# trinamic-controller-dribbler.net
KiCad netlist of a schematic drawn in Altium Designer
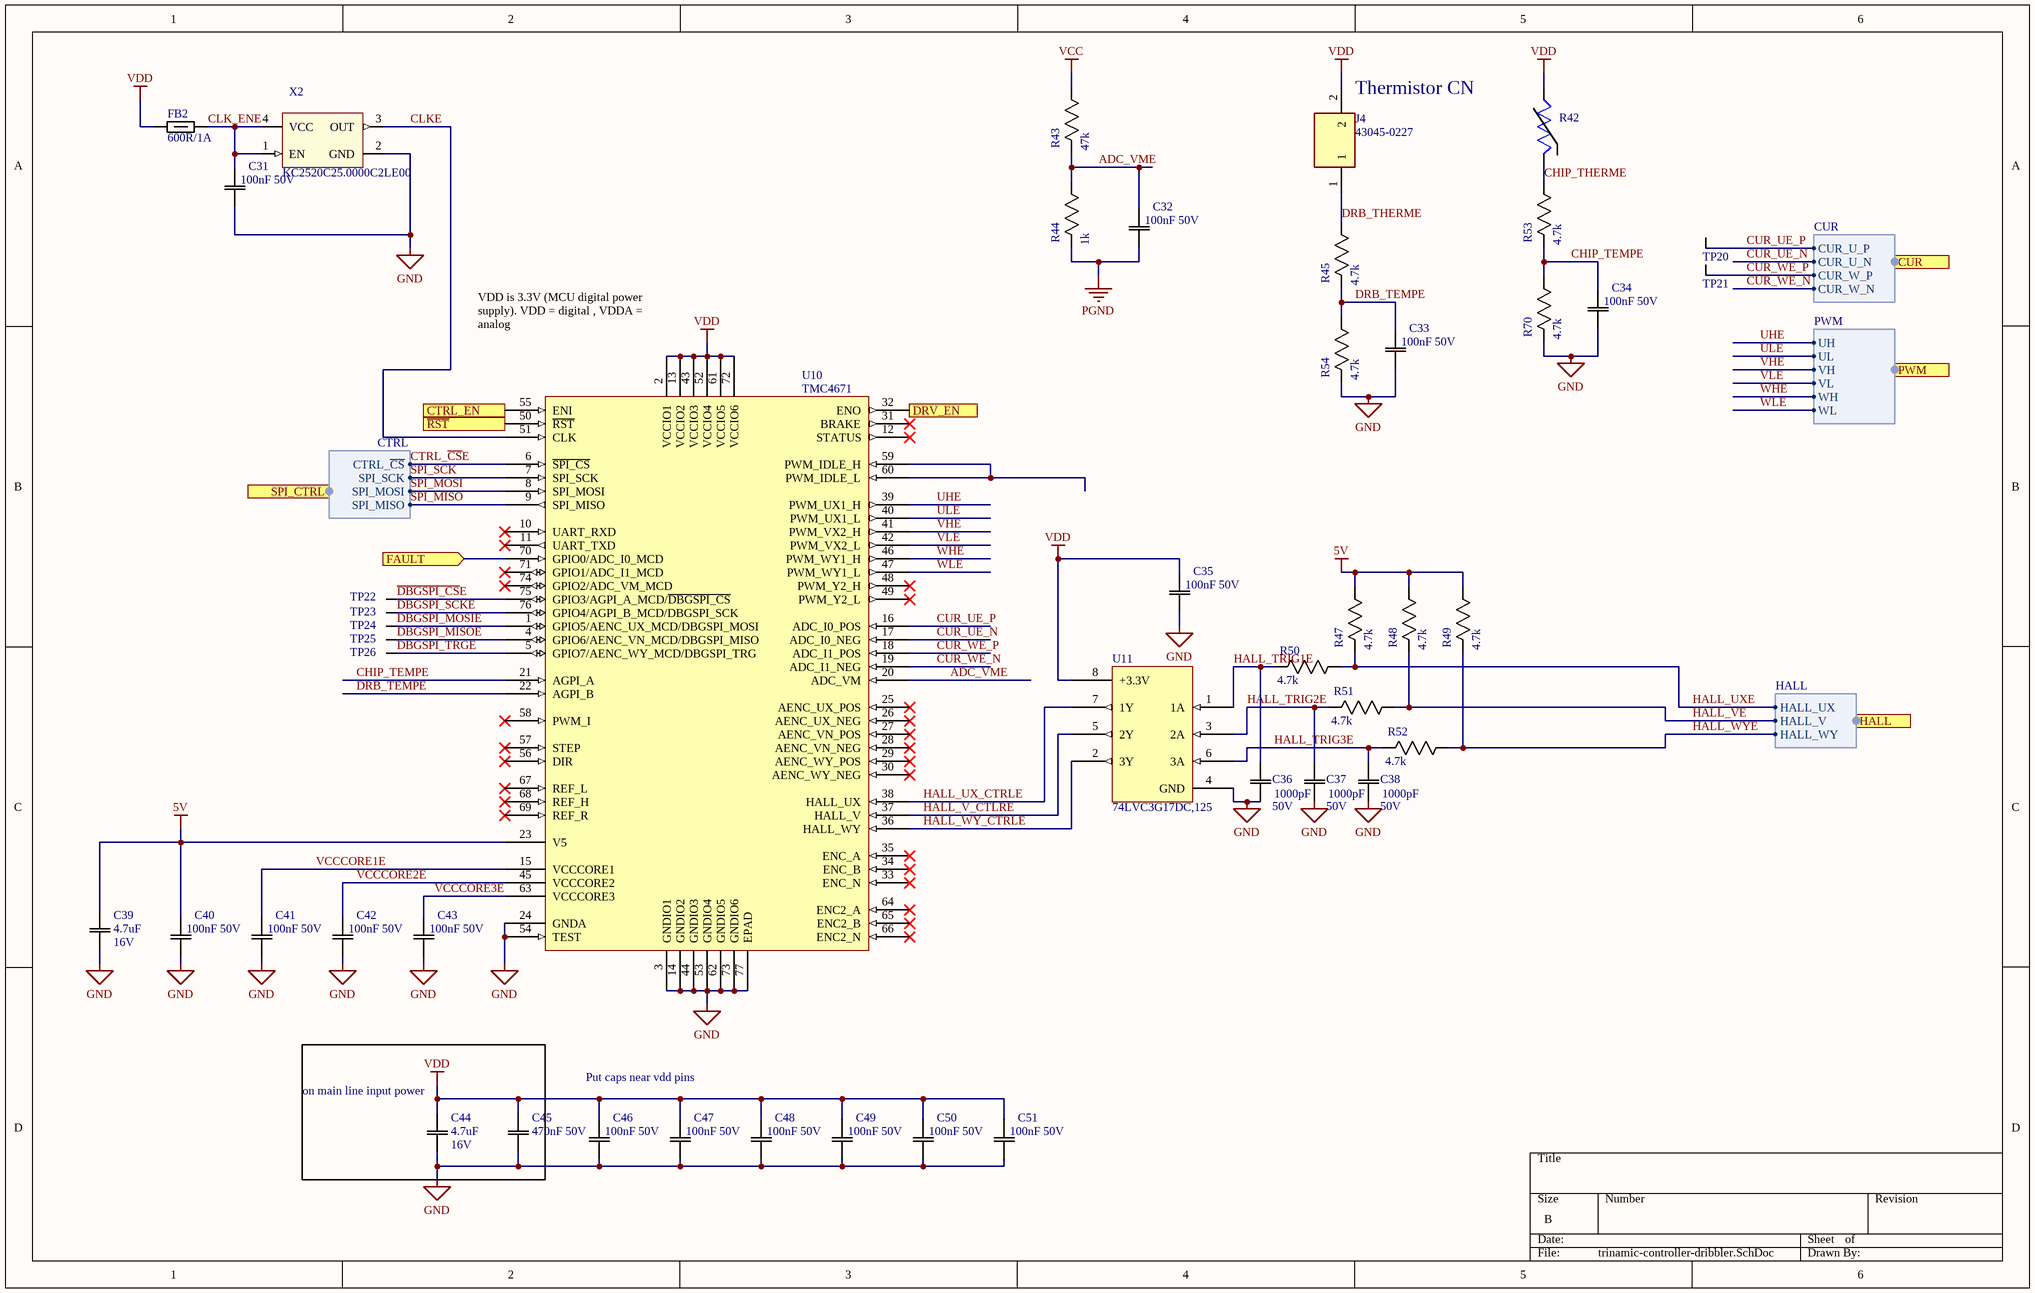
[diagram p0: trinamic-controller-dribbler.SchDoc]

(export (version "E")
  (design (tool "Eeschema 10.0.6"))
  (components
    (comp (ref "C31")
      (value "100nF 50V")
      (footprint "0603")
      (description "Default Symbol for Capacitors")
      (fields (field (name "TOLERANCE") "10%") (field (name "PART NUMBER") "CAP 100nF 50V"))
      (libsource (lib "capacitor_library") (part "CAP_Default"))
    )
    (comp (ref "C32")
      (value "100nF 50V")
      (footprint "0603")
      (description "Default Symbol for Capacitors")
      (fields (field (name "TOLERANCE") "10%") (field (name "PART NUMBER") "CAP 100nF 50V"))
      (libsource (lib "capacitor_library") (part "CAP_Default"))
    )
    (comp (ref "C33")
      (value "100nF 50V")
      (footprint "0603")
      (description "Default Symbol for Capacitors")
      (fields (field (name "TOLERANCE") "10%") (field (name "PART NUMBER") "CAP 100nF 50V"))
      (libsource (lib "capacitor_library") (part "CAP_Default"))
    )
    (comp (ref "C34")
      (value "100nF 50V")
      (footprint "0603")
      (description "Default Symbol for Capacitors")
      (fields (field (name "TOLERANCE") "10%") (field (name "PART NUMBER") "CAP 100nF 50V"))
      (libsource (lib "capacitor_library") (part "CAP_Default"))
    )
    (comp (ref "C35")
      (value "100nF 50V")
      (footprint "0603")
      (description "Default Symbol for Capacitors")
      (fields (field (name "TOLERANCE") "10%") (field (name "PART NUMBER") "CAP 100nF 50V"))
      (libsource (lib "capacitor_library") (part "CAP_Default"))
    )
    (comp (ref "C36")
      (value "1000pF")
      (footprint "0603")
      (description "Default Symbol for Capacitors")
      (fields
        (field (name "TOLERANCE") "10%")
        (field (name "RATING") "50V")
        (field (name "PART NUMBER") "CAP 1000pF 50V")
      )
      (libsource (lib "capacitor_library") (part "CAP_Default"))
    )
    (comp (ref "C37")
      (value "1000pF")
      (footprint "0603")
      (description "Default Symbol for Capacitors")
      (fields
        (field (name "TOLERANCE") "10%")
        (field (name "RATING") "50V")
        (field (name "PART NUMBER") "CAP 1000pF 50V")
      )
      (libsource (lib "capacitor_library") (part "CAP_Default"))
    )
    (comp (ref "C38")
      (value "1000pF")
      (footprint "0603")
      (description "Default Symbol for Capacitors")
      (fields
        (field (name "TOLERANCE") "10%")
        (field (name "RATING") "50V")
        (field (name "PART NUMBER") "CAP 1000pF 50V")
      )
      (libsource (lib "capacitor_library") (part "CAP_Default"))
    )
    (comp (ref "C39")
      (value "4.7uF")
      (footprint "0603")
      (description "Default Symbol for Capacitors")
      (fields
        (field (name "TOLERANCE") "10%")
        (field (name "RATING") "16V")
        (field (name "PART NUMBER") "CAP 4.7uF 16V")
      )
      (libsource (lib "capacitor_library") (part "CAP_Default"))
    )
    (comp (ref "C40")
      (value "100nF 50V")
      (footprint "0603")
      (description "Default Symbol for Capacitors")
      (fields (field (name "TOLERANCE") "10%") (field (name "PART NUMBER") "CAP 100nF 50V"))
      (libsource (lib "capacitor_library") (part "CAP_Default"))
    )
    (comp (ref "C41")
      (value "100nF 50V")
      (footprint "0603")
      (description "Default Symbol for Capacitors")
      (fields (field (name "TOLERANCE") "10%") (field (name "PART NUMBER") "CAP 100nF 50V"))
      (libsource (lib "capacitor_library") (part "CAP_Default"))
    )
    (comp (ref "C42")
      (value "100nF 50V")
      (footprint "0603")
      (description "Default Symbol for Capacitors")
      (fields (field (name "TOLERANCE") "10%") (field (name "PART NUMBER") "CAP 100nF 50V"))
      (libsource (lib "capacitor_library") (part "CAP_Default"))
    )
    (comp (ref "C43")
      (value "100nF 50V")
      (footprint "0603")
      (description "Default Symbol for Capacitors")
      (fields (field (name "TOLERANCE") "10%") (field (name "PART NUMBER") "CAP 100nF 50V"))
      (libsource (lib "capacitor_library") (part "CAP_Default"))
    )
    (comp (ref "C44")
      (value "4.7uF")
      (footprint "0603")
      (description "Default Symbol for Capacitors")
      (fields
        (field (name "TOLERANCE") "10%")
        (field (name "RATING") "16V")
        (field (name "PART NUMBER") "CAP 4.7uF 16V")
      )
      (libsource (lib "capacitor_library") (part "CAP_Default"))
    )
    (comp (ref "C45")
      (value "470nF 50V")
      (footprint "0603")
      (description "Default Symbol for Capacitors")
      (fields (field (name "TOLERANCE") "10%") (field (name "PART NUMBER") "CAP 470nF 50V"))
      (libsource (lib "capacitor_library") (part "CAP_Default"))
    )
    (comp (ref "C46")
      (value "100nF 50V")
      (footprint "0603")
      (description "Default Symbol for Capacitors")
      (fields (field (name "TOLERANCE") "10%") (field (name "PART NUMBER") "CAP 100nF 50V"))
      (libsource (lib "capacitor_library") (part "CAP_Default"))
    )
    (comp (ref "C47")
      (value "100nF 50V")
      (footprint "0603")
      (description "Default Symbol for Capacitors")
      (fields (field (name "TOLERANCE") "10%") (field (name "PART NUMBER") "CAP 100nF 50V"))
      (libsource (lib "capacitor_library") (part "CAP_Default"))
    )
    (comp (ref "C48")
      (value "100nF 50V")
      (footprint "0603")
      (description "Default Symbol for Capacitors")
      (fields (field (name "TOLERANCE") "10%") (field (name "PART NUMBER") "CAP 100nF 50V"))
      (libsource (lib "capacitor_library") (part "CAP_Default"))
    )
    (comp (ref "C49")
      (value "100nF 50V")
      (footprint "0603")
      (description "Default Symbol for Capacitors")
      (fields (field (name "TOLERANCE") "10%") (field (name "PART NUMBER") "CAP 100nF 50V"))
      (libsource (lib "capacitor_library") (part "CAP_Default"))
    )
    (comp (ref "C50")
      (value "100nF 50V")
      (footprint "0603")
      (description "Default Symbol for Capacitors")
      (fields (field (name "TOLERANCE") "10%") (field (name "PART NUMBER") "CAP 100nF 50V"))
      (libsource (lib "capacitor_library") (part "CAP_Default"))
    )
    (comp (ref "C51")
      (value "100nF 50V")
      (footprint "0603")
      (description "Default Symbol for Capacitors")
      (fields (field (name "TOLERANCE") "10%") (field (name "PART NUMBER") "CAP 100nF 50V"))
      (libsource (lib "capacitor_library") (part "CAP_Default"))
    )
    (comp (ref "FB2")
      (value "600R/1A")
      (footprint "0603")
      (fields (field (name "PART NUMBER") "FERRITE BEAD 200 MOHM 0603 1LN"))
      (libsource (lib "Inductor_Library") (part "FERRITE BEAD 200 MOHM 0603 1LN"))
    )
    (comp (ref "J4")
      (value "43045-0227")
      (footprint "MOLEX_0430450227")
      (description "Molex 43045-0227 2POS Microfit\r\ndual row, Vertical")
      (fields (field (name "PART NUMBER") "CN HDR 2POS Molex 43045-0227"))
      (libsource (lib "Connector_Library") (part "CN HDR 2POS Molex 43045-0227"))
    )
    (comp (ref "R42")
      (value "RES NTC 10k")
      (footprint "0603")
      (fields (field (name "PART NUMBER") "RES NTC 10k CHIP") (field (name "TOLERANCE") "1%"))
      (libsource (lib "Resistor_Library") (part "RES NTC 10k"))
    )
    (comp (ref "R43")
      (value "47k")
      (footprint "0603")
      (description "Default Resistor Symbol")
      (fields (field (name "TOLERANCE") "1%") (field (name "PART NUMBER") "RES 47k 1/8W - 1%"))
      (libsource (lib "") (part "RES_DEFAULT_2"))
    )
    (comp (ref "R44")
      (value "1k")
      (footprint "0603")
      (description "Default Resistor Symbol")
      (fields (field (name "TOLERANCE") "1%") (field (name "PART NUMBER") "RES 1k 1/8W - 1%"))
      (libsource (lib "") (part "RES_DEFAULT_1"))
    )
    (comp (ref "R45")
      (value "4.7k")
      (footprint "0603")
      (description "Default Resistor Symbol")
      (fields (field (name "TOLERANCE") "1%") (field (name "PART NUMBER") "RES 4.7k 1/8W - 1%"))
      (libsource (lib "") (part "RES_DEFAULT_1"))
    )
    (comp (ref "R47")
      (value "4.7k")
      (footprint "0603")
      (description "Default Resistor Symbol")
      (fields (field (name "TOLERANCE") "5%") (field (name "PART NUMBER") "RES 4.7k 1/8W - 5%"))
      (libsource (lib "Resistor_Library") (part "RES_DEFAULT"))
    )
    (comp (ref "R48")
      (value "4.7k")
      (footprint "0603")
      (description "Default Resistor Symbol")
      (fields (field (name "TOLERANCE") "5%") (field (name "PART NUMBER") "RES 4.7k 1/8W - 5%"))
      (libsource (lib "Resistor_Library") (part "RES_DEFAULT"))
    )
    (comp (ref "R49")
      (value "4.7k")
      (footprint "0603")
      (description "Default Resistor Symbol")
      (fields (field (name "TOLERANCE") "5%") (field (name "PART NUMBER") "RES 4.7k 1/8W - 5%"))
      (libsource (lib "") (part "RES_DEFAULT_1"))
    )
    (comp (ref "R50")
      (value "4.7k")
      (footprint "0603")
      (description "Default Resistor Symbol")
      (fields (field (name "TOLERANCE") "5%") (field (name "PART NUMBER") "RES 4.7k 1/8W - 5%"))
      (libsource (lib "Resistor_Library") (part "RES_DEFAULT"))
    )
    (comp (ref "R51")
      (value "4.7k")
      (footprint "0603")
      (description "Default Resistor Symbol")
      (fields (field (name "TOLERANCE") "5%") (field (name "PART NUMBER") "RES 4.7k 1/8W - 5%"))
      (libsource (lib "Resistor_Library") (part "RES_DEFAULT"))
    )
    (comp (ref "R52")
      (value "4.7k")
      (footprint "0603")
      (description "Default Resistor Symbol")
      (fields (field (name "TOLERANCE") "5%") (field (name "PART NUMBER") "RES 4.7k 1/8W - 5%"))
      (libsource (lib "Resistor_Library") (part "RES_DEFAULT"))
    )
    (comp (ref "R53")
      (value "4.7k")
      (footprint "0603")
      (description "Default Resistor Symbol")
      (fields (field (name "TOLERANCE") "1%") (field (name "PART NUMBER") "RES 4.7k 1/8W - 1%"))
      (libsource (lib "") (part "RES_DEFAULT_1"))
    )
    (comp (ref "R54")
      (value "4.7k")
      (footprint "0603")
      (description "Default Resistor Symbol")
      (fields (field (name "TOLERANCE") "1%") (field (name "PART NUMBER") "RES 4.7k 1/8W - 1%"))
      (libsource (lib "") (part "RES_DEFAULT_1"))
    )
    (comp (ref "R70")
      (value "4.7k")
      (footprint "0603")
      (description "Default Resistor Symbol")
      (fields (field (name "TOLERANCE") "1%") (field (name "PART NUMBER") "RES 4.7k 1/8W - 1%"))
      (libsource (lib "") (part "RES_DEFAULT_1"))
    )
    (comp (ref "TP20")
      (value "C_UE")
      (footprint "TP")
      (fields (field (name "PART NUMBER") "Test Point (Via)"))
      (libsource (lib "IC_Library") (part "Test Point (Via)"))
    )
    (comp (ref "TP21")
      (value "C_WE")
      (footprint "TP")
      (fields (field (name "PART NUMBER") "Test Point (Via)"))
      (libsource (lib "IC_Library") (part "Test Point (Via)"))
    )
    (comp (ref "TP22")
      (value "DBG_CS")
      (footprint "TP")
      (fields (field (name "PART NUMBER") "Test Point (Via)"))
      (libsource (lib "IC_Library") (part "Test Point (Via)"))
    )
    (comp (ref "TP23")
      (value "DBG_SCK")
      (footprint "TP")
      (fields (field (name "PART NUMBER") "Test Point (Via)"))
      (libsource (lib "IC_Library") (part "Test Point (Via)"))
    )
    (comp (ref "TP24")
      (value "DBG_MOSI")
      (footprint "TP")
      (fields (field (name "PART NUMBER") "Test Point (Via)"))
      (libsource (lib "IC_Library") (part "Test Point (Via)"))
    )
    (comp (ref "TP25")
      (value "DBG_MISO")
      (footprint "TP")
      (fields (field (name "PART NUMBER") "Test Point (Via)"))
      (libsource (lib "IC_Library") (part "Test Point (Via)"))
    )
    (comp (ref "TP26")
      (value "DBG_TRG")
      (footprint "TP")
      (fields (field (name "PART NUMBER") "Test Point (Via)"))
      (libsource (lib "IC_Library") (part "Test Point (Via)"))
    )
    (comp (ref "U10")
      (value "TMC4671")
      (footprint "QFN40P1050X650X90_HS-77N")
      (description "Motor Driver, -40 To 125Deg C Rohs Compliant: Yes")
      (libsource (lib "IC_Library") (part "TMC4671"))
    )
    (comp (ref "U11")
      (value "74LVC3G17DC,125")
      (footprint "8-VSSOP")
      (description "IC BUFFER TRIPLE SCHMITT TRIGGER 5.5V VSSOP-8")
      (fields (field (name "PART NUMBER") "IC 74LVC3G17DC,125"))
      (libsource (lib "IC_Library") (part "IC 74LVC3G17DC,125"))
    )
    (comp (ref "X2")
      (value "KC2520C25.0000C2LE00")
      (footprint "KC2520C25.0000C2LE00")
      (description "Oscillator XO 25MHz ±15ppm 15pF CMOS 55% 2.5V/3.3V 4-Pin Mini-CSMD T/R")
      (fields (field (name "PART NUMBER") "XTAL OSC 25MHz 3.3V"))
      (libsource (lib "Oscillator_Library") (part "XTAL OSC 25MHz 3.3V"))
    )
  )
  (nets
    (net (code "5") (name "/ADC_VME") (class "Default")
      (node (ref "C32") (pin "2") (pinfunction "C2_2") (pintype "passive"))
      (node (ref "R43") (pin "2") (pinfunction "R2_2") (pintype "passive"))
      (node (ref "R44") (pin "1") (pinfunction "R1_1") (pintype "passive"))
      (node (ref "U10") (pin "20") (pinfunction "ADC_VM_20") (pintype "input"))
    )
    (net (code "6") (name "/CHIP_TEMPE") (class "Default")
      (node (ref "C34") (pin "2") (pinfunction "C2_2") (pintype "passive"))
      (node (ref "R53") (pin "2") (pinfunction "R2_2") (pintype "passive"))
      (node (ref "R70") (pin "1") (pinfunction "R1_1") (pintype "passive"))
      (node (ref "U10") (pin "21") (pinfunction "AGPI_A_21") (pintype "input"))
    )
    (net (code "7") (name "/CHIP_THERME") (class "Default")
      (node (ref "R42") (pin "1") (pinfunction "1_1") (pintype "passive"))
      (node (ref "R53") (pin "1") (pinfunction "R1_1") (pintype "passive"))
    )
    (net (code "8") (name "/CLKE") (class "Default")
      (node (ref "U10") (pin "51") (pinfunction "CLK_51") (pintype "input"))
      (node (ref "X2") (pin "3") (pinfunction "OUT_3") (pintype "output"))
    )
    (net (code "9") (name "/CLK_ENE") (class "Default")
      (node (ref "C31") (pin "2") (pinfunction "C2_2") (pintype "passive"))
      (node (ref "FB2") (pin "2") (pinfunction "2_2") (pintype "passive"))
      (node (ref "X2") (pin "1") (pinfunction "EN_1") (pintype "input"))
      (node (ref "X2") (pin "4") (pinfunction "VCC_4") (pintype "power_in"))
    )
    (net (code "10") (name "/CTRL_EN") (class "Default")
      (node (ref "U10") (pin "55") (pinfunction "ENI_55") (pintype "input"))
    )
    (net (code "11") (name "/CTRL_~{CS}E") (class "Default")
      (node (ref "U10") (pin "6") (pinfunction "~{SPI_CS}_6") (pintype "input"))
    )
    (net (code "12") (name "/CUR_UE_N") (class "Default")
      (node (ref "U10") (pin "17") (pinfunction "ADC_I0_NEG_17") (pintype "input"))
    )
    (net (code "13") (name "/CUR_UE_P") (class "Default")
      (node (ref "TP20") (pin "1") (pinfunction "1_1") (pintype "passive"))
      (node (ref "U10") (pin "16") (pinfunction "ADC_I0_POS_16") (pintype "input"))
    )
    (net (code "14") (name "/CUR_WE_N") (class "Default")
      (node (ref "U10") (pin "19") (pinfunction "ADC_I1_NEG_19") (pintype "input"))
    )
    (net (code "15") (name "/CUR_WE_P") (class "Default")
      (node (ref "TP21") (pin "1") (pinfunction "1_1") (pintype "passive"))
      (node (ref "U10") (pin "18") (pinfunction "ADC_I1_POS_18") (pintype "input"))
    )
    (net (code "16") (name "/DBGSPI_MISOE") (class "Default")
      (node (ref "TP25") (pin "1") (pinfunction "1_1") (pintype "passive"))
      (node (ref "U10") (pin "4") (pinfunction "GPIO6/AENC_VN_MCD/DBGSPI_MISO_4") (pintype "bidirectional"))
    )
    (net (code "17") (name "/DBGSPI_MOSIE") (class "Default")
      (node (ref "TP24") (pin "1") (pinfunction "1_1") (pintype "passive"))
      (node (ref "U10") (pin "1") (pinfunction "GPIO5/AENC_UX_MCD/DBGSPI_MOSI_1") (pintype "bidirectional"))
    )
    (net (code "18") (name "/DBGSPI_SCKE") (class "Default")
      (node (ref "TP23") (pin "1") (pinfunction "1_1") (pintype "passive"))
      (node (ref "U10") (pin "76") (pinfunction "GPIO4/AGPI_B_MCD/DBGSPI_SCK_76") (pintype "bidirectional"))
    )
    (net (code "19") (name "/DBGSPI_TRGE") (class "Default")
      (node (ref "TP26") (pin "1") (pinfunction "1_1") (pintype "passive"))
      (node (ref "U10") (pin "5") (pinfunction "GPIO7/AENC_WY_MCD/DBGSPI_TRG_5") (pintype "bidirectional"))
    )
    (net (code "20") (name "/DRB_TEMPE") (class "Default")
      (node (ref "C33") (pin "2") (pinfunction "C2_2") (pintype "passive"))
      (node (ref "R45") (pin "2") (pinfunction "R2_2") (pintype "passive"))
      (node (ref "R54") (pin "1") (pinfunction "R1_1") (pintype "passive"))
      (node (ref "U10") (pin "22") (pinfunction "AGPI_B_22") (pintype "input"))
    )
    (net (code "21") (name "/DRB_THERME") (class "Default")
      (node (ref "J4") (pin "1") (pinfunction "1_1") (pintype "passive"))
      (node (ref "R45") (pin "1") (pinfunction "R1_1") (pintype "passive"))
    )
    (net (code "22") (name "/DRV_EN") (class "Default")
      (node (ref "U10") (pin "32") (pinfunction "ENO_32") (pintype "output"))
    )
    (net (code "23") (name "/FAULT") (class "Default")
      (node (ref "U10") (pin "70") (pinfunction "GPIO0/ADC_I0_MCD_70") (pintype "input"))
    )
    (net (code "24") (name "/HALL_TRIG1E") (class "Default")
      (node (ref "C36") (pin "2") (pinfunction "C2_2") (pintype "passive"))
      (node (ref "R50") (pin "2") (pinfunction "R2_2") (pintype "passive"))
      (node (ref "U11") (pin "1") (pinfunction "1A_1") (pintype "input"))
    )
    (net (code "25") (name "/HALL_TRIG2E") (class "Default")
      (node (ref "C37") (pin "2") (pinfunction "C2_2") (pintype "passive"))
      (node (ref "R51") (pin "2") (pinfunction "R2_2") (pintype "passive"))
      (node (ref "U11") (pin "3") (pinfunction "2A_3") (pintype "input"))
    )
    (net (code "26") (name "/HALL_TRIG3E") (class "Default")
      (node (ref "C38") (pin "2") (pinfunction "C2_2") (pintype "passive"))
      (node (ref "R52") (pin "2") (pinfunction "R2_2") (pintype "passive"))
      (node (ref "U11") (pin "6") (pinfunction "3A_6") (pintype "input"))
    )
    (net (code "27") (name "/HALL_UXE") (class "Default")
      (node (ref "R47") (pin "2") (pinfunction "R2_2") (pintype "passive"))
      (node (ref "R50") (pin "1") (pinfunction "R1_1") (pintype "passive"))
    )
    (net (code "28") (name "/HALL_UX_CTRLE") (class "Default")
      (node (ref "U10") (pin "38") (pinfunction "HALL_UX_38") (pintype "input"))
      (node (ref "U11") (pin "7") (pinfunction "1Y_7") (pintype "output"))
    )
    (net (code "29") (name "/HALL_VE") (class "Default")
      (node (ref "R48") (pin "2") (pinfunction "R2_2") (pintype "passive"))
      (node (ref "R51") (pin "1") (pinfunction "R1_1") (pintype "passive"))
    )
    (net (code "30") (name "/HALL_V_CTLRE") (class "Default")
      (node (ref "U10") (pin "37") (pinfunction "HALL_V_37") (pintype "input"))
      (node (ref "U11") (pin "5") (pinfunction "2Y_5") (pintype "output"))
    )
    (net (code "31") (name "/HALL_WYE") (class "Default")
      (node (ref "R49") (pin "2") (pinfunction "R2_2") (pintype "passive"))
      (node (ref "R52") (pin "1") (pinfunction "R1_1") (pintype "passive"))
    )
    (net (code "32") (name "/HALL_WY_CTRLE") (class "Default")
      (node (ref "U10") (pin "36") (pinfunction "HALL_WY_36") (pintype "input"))
      (node (ref "U11") (pin "2") (pinfunction "3Y_2") (pintype "output"))
    )
    (net (code "33") (name "/SPI_MISO") (class "Default")
      (node (ref "U10") (pin "9") (pinfunction "SPI_MISO_9") (pintype "output"))
    )
    (net (code "34") (name "/SPI_MOSI") (class "Default")
      (node (ref "U10") (pin "8") (pinfunction "SPI_MOSI_8") (pintype "input"))
    )
    (net (code "35") (name "/SPI_SCK") (class "Default")
      (node (ref "U10") (pin "7") (pinfunction "SPI_SCK_7") (pintype "input"))
    )
    (net (code "36") (name "/UHE") (class "Default")
      (node (ref "U10") (pin "39") (pinfunction "PWM_UX1_H_39") (pintype "output"))
    )
    (net (code "37") (name "/ULE") (class "Default")
      (node (ref "U10") (pin "40") (pinfunction "PWM_UX1_L_40") (pintype "output"))
    )
    (net (code "38") (name "/VCCCORE1E") (class "Default")
      (node (ref "C41") (pin "2") (pinfunction "C2_2") (pintype "passive"))
      (node (ref "U10") (pin "15") (pinfunction "VCCCORE1_15") (pintype "power_in"))
    )
    (net (code "39") (name "/VCCCORE2E") (class "Default")
      (node (ref "C42") (pin "2") (pinfunction "C2_2") (pintype "passive"))
      (node (ref "U10") (pin "45") (pinfunction "VCCCORE2_45") (pintype "power_in"))
    )
    (net (code "40") (name "/VCCCORE3E") (class "Default")
      (node (ref "C43") (pin "2") (pinfunction "C2_2") (pintype "passive"))
      (node (ref "U10") (pin "63") (pinfunction "VCCCORE3_63") (pintype "power_in"))
    )
    (net (code "41") (name "/VHE") (class "Default")
      (node (ref "U10") (pin "41") (pinfunction "PWM_VX2_H_41") (pintype "output"))
    )
    (net (code "42") (name "/VLE") (class "Default")
      (node (ref "U10") (pin "42") (pinfunction "PWM_VX2_L_42") (pintype "output"))
    )
    (net (code "43") (name "/WHE") (class "Default")
      (node (ref "U10") (pin "46") (pinfunction "PWM_WY1_H_46") (pintype "output"))
    )
    (net (code "44") (name "/WLE") (class "Default")
      (node (ref "U10") (pin "47") (pinfunction "PWM_WY1_L_47") (pintype "output"))
    )
    (net (code "49") (name "/~{DBGSPI_CS}E") (class "Default")
      (node (ref "TP22") (pin "1") (pinfunction "1_1") (pintype "passive"))
      (node (ref "U10") (pin "75") (pinfunction "GPIO3/AGPI_A_MCD/~{DBGSPI_CS}_75") (pintype "bidirectional"))
    )
    (net (code "50") (name "/~{RST}") (class "Default")
      (node (ref "U10") (pin "50") (pinfunction "~{RST}_50") (pintype "input"))
    )
    (net (code "51") (name "5V") (class "Default")
      (node (ref "C39") (pin "2") (pinfunction "C2_2") (pintype "passive"))
      (node (ref "C40") (pin "2") (pinfunction "C2_2") (pintype "passive"))
      (node (ref "R47") (pin "1") (pinfunction "R1_1") (pintype "passive"))
      (node (ref "R48") (pin "1") (pinfunction "R1_1") (pintype "passive"))
      (node (ref "R49") (pin "1") (pinfunction "R1_1") (pintype "passive"))
      (node (ref "U10") (pin "23") (pinfunction "V5_23") (pintype "power_in"))
    )
    (net (code "52") (name "GND") (class "Default")
      (node (ref "C31") (pin "1") (pinfunction "C1_1") (pintype "passive"))
      (node (ref "C33") (pin "1") (pinfunction "C1_1") (pintype "passive"))
      (node (ref "C34") (pin "1") (pinfunction "C1_1") (pintype "passive"))
      (node (ref "C35") (pin "1") (pinfunction "C1_1") (pintype "passive"))
      (node (ref "C36") (pin "1") (pinfunction "C1_1") (pintype "passive"))
      (node (ref "C37") (pin "1") (pinfunction "C1_1") (pintype "passive"))
      (node (ref "C38") (pin "1") (pinfunction "C1_1") (pintype "passive"))
      (node (ref "C39") (pin "1") (pinfunction "C1_1") (pintype "passive"))
      (node (ref "C40") (pin "1") (pinfunction "C1_1") (pintype "passive"))
      (node (ref "C41") (pin "1") (pinfunction "C1_1") (pintype "passive"))
      (node (ref "C42") (pin "1") (pinfunction "C1_1") (pintype "passive"))
      (node (ref "C43") (pin "1") (pinfunction "C1_1") (pintype "passive"))
      (node (ref "C44") (pin "1") (pinfunction "C1_1") (pintype "passive"))
      (node (ref "C45") (pin "1") (pinfunction "C1_1") (pintype "passive"))
      (node (ref "C46") (pin "1") (pinfunction "C1_1") (pintype "passive"))
      (node (ref "C47") (pin "1") (pinfunction "C1_1") (pintype "passive"))
      (node (ref "C48") (pin "1") (pinfunction "C1_1") (pintype "passive"))
      (node (ref "C49") (pin "1") (pinfunction "C1_1") (pintype "passive"))
      (node (ref "C50") (pin "1") (pinfunction "C1_1") (pintype "passive"))
      (node (ref "C51") (pin "1") (pinfunction "C1_1") (pintype "passive"))
      (node (ref "R54") (pin "2") (pinfunction "R2_2") (pintype "passive"))
      (node (ref "R70") (pin "2") (pinfunction "R2_2") (pintype "passive"))
      (node (ref "U10") (pin "14") (pinfunction "GNDIO2_14") (pintype "power_in"))
      (node (ref "U10") (pin "24") (pinfunction "GNDA_24") (pintype "power_in"))
      (node (ref "U10") (pin "3") (pinfunction "GNDIO1_3") (pintype "power_in"))
      (node (ref "U10") (pin "44") (pinfunction "GNDIO3_44") (pintype "power_in"))
      (node (ref "U10") (pin "53") (pinfunction "GNDIO4_53") (pintype "power_in"))
      (node (ref "U10") (pin "54") (pinfunction "TEST_54") (pintype "input"))
      (node (ref "U10") (pin "62") (pinfunction "GNDIO5_62") (pintype "power_in"))
      (node (ref "U10") (pin "73") (pinfunction "GNDIO6_73") (pintype "power_in"))
      (node (ref "U10") (pin "77") (pinfunction "EPAD_77") (pintype "passive"))
      (node (ref "U11") (pin "4") (pinfunction "GND_4") (pintype "power_in"))
      (node (ref "X2") (pin "2") (pinfunction "GND_2") (pintype "power_in"))
    )
    (net (code "53") (name "Net-(U10-PWM_IDLE_H)") (class "Default")
      (node (ref "U10") (pin "59") (pinfunction "PWM_IDLE_H_59") (pintype "input"))
      (node (ref "U10") (pin "60") (pinfunction "PWM_IDLE_L_60") (pintype "input"))
    )
    (net (code "54") (name "PGND") (class "Default")
      (node (ref "C32") (pin "1") (pinfunction "C1_1") (pintype "passive"))
      (node (ref "R44") (pin "2") (pinfunction "R2_2") (pintype "passive"))
    )
    (net (code "55") (name "VCC") (class "Default")
      (node (ref "R43") (pin "1") (pinfunction "R1_1") (pintype "passive"))
    )
    (net (code "56") (name "VDD") (class "Default")
      (node (ref "C35") (pin "2") (pinfunction "C2_2") (pintype "passive"))
      (node (ref "C44") (pin "2") (pinfunction "C2_2") (pintype "passive"))
      (node (ref "C45") (pin "2") (pinfunction "C2_2") (pintype "passive"))
      (node (ref "C46") (pin "2") (pinfunction "C2_2") (pintype "passive"))
      (node (ref "C47") (pin "2") (pinfunction "C2_2") (pintype "passive"))
      (node (ref "C48") (pin "2") (pinfunction "C2_2") (pintype "passive"))
      (node (ref "C49") (pin "2") (pinfunction "C2_2") (pintype "passive"))
      (node (ref "C50") (pin "2") (pinfunction "C2_2") (pintype "passive"))
      (node (ref "C51") (pin "2") (pinfunction "C2_2") (pintype "passive"))
      (node (ref "FB2") (pin "1") (pinfunction "1_1") (pintype "passive"))
      (node (ref "J4") (pin "2") (pinfunction "2_2") (pintype "passive"))
      (node (ref "R42") (pin "2") (pinfunction "2_2") (pintype "passive"))
      (node (ref "U10") (pin "13") (pinfunction "VCCIO2_13") (pintype "power_in"))
      (node (ref "U10") (pin "2") (pinfunction "VCCIO1_2") (pintype "power_in"))
      (node (ref "U10") (pin "43") (pinfunction "VCCIO3_43") (pintype "power_in"))
      (node (ref "U10") (pin "52") (pinfunction "VCCIO4_52") (pintype "power_in"))
      (node (ref "U10") (pin "61") (pinfunction "VCCIO5_61") (pintype "power_in"))
      (node (ref "U10") (pin "72") (pinfunction "VCCIO6_72") (pintype "power_in"))
      (node (ref "U11") (pin "8") (pinfunction "+3.3V_8") (pintype "power_in"))
    )
    (net (code "57") (name "unconnected-(U10-AENC_UX_NEG-Pad26)") (class "Default")
      (node (ref "U10") (pin "26") (pinfunction "AENC_UX_NEG_26") (pintype "input+no_connect"))
    )
    (net (code "58") (name "unconnected-(U10-AENC_UX_POS-Pad25)") (class "Default")
      (node (ref "U10") (pin "25") (pinfunction "AENC_UX_POS_25") (pintype "input+no_connect"))
    )
    (net (code "59") (name "unconnected-(U10-AENC_VN_NEG-Pad28)") (class "Default")
      (node (ref "U10") (pin "28") (pinfunction "AENC_VN_NEG_28") (pintype "input+no_connect"))
    )
    (net (code "60") (name "unconnected-(U10-AENC_VN_POS-Pad27)") (class "Default")
      (node (ref "U10") (pin "27") (pinfunction "AENC_VN_POS_27") (pintype "input+no_connect"))
    )
    (net (code "61") (name "unconnected-(U10-AENC_WY_NEG-Pad30)") (class "Default")
      (node (ref "U10") (pin "30") (pinfunction "AENC_WY_NEG_30") (pintype "input+no_connect"))
    )
    (net (code "62") (name "unconnected-(U10-AENC_WY_POS-Pad29)") (class "Default")
      (node (ref "U10") (pin "29") (pinfunction "AENC_WY_POS_29") (pintype "input+no_connect"))
    )
    (net (code "63") (name "unconnected-(U10-BRAKE-Pad31)") (class "Default")
      (node (ref "U10") (pin "31") (pinfunction "BRAKE_31") (pintype "output+no_connect"))
    )
    (net (code "64") (name "unconnected-(U10-DIR-Pad56)") (class "Default")
      (node (ref "U10") (pin "56") (pinfunction "DIR_56") (pintype "input+no_connect"))
    )
    (net (code "65") (name "unconnected-(U10-ENC2_A-Pad64)") (class "Default")
      (node (ref "U10") (pin "64") (pinfunction "ENC2_A_64") (pintype "input+no_connect"))
    )
    (net (code "66") (name "unconnected-(U10-ENC2_B-Pad65)") (class "Default")
      (node (ref "U10") (pin "65") (pinfunction "ENC2_B_65") (pintype "input+no_connect"))
    )
    (net (code "67") (name "unconnected-(U10-ENC2_N-Pad66)") (class "Default")
      (node (ref "U10") (pin "66") (pinfunction "ENC2_N_66") (pintype "input+no_connect"))
    )
    (net (code "68") (name "unconnected-(U10-ENC_A-Pad35)") (class "Default")
      (node (ref "U10") (pin "35") (pinfunction "ENC_A_35") (pintype "input+no_connect"))
    )
    (net (code "69") (name "unconnected-(U10-ENC_B-Pad34)") (class "Default")
      (node (ref "U10") (pin "34") (pinfunction "ENC_B_34") (pintype "input+no_connect"))
    )
    (net (code "70") (name "unconnected-(U10-ENC_N-Pad33)") (class "Default")
      (node (ref "U10") (pin "33") (pinfunction "ENC_N_33") (pintype "input+no_connect"))
    )
    (net (code "71") (name "unconnected-(U10-GPIO1{slash}ADC_I1_MCD-Pad71)") (class "Default")
      (node (ref "U10") (pin "71") (pinfunction "GPIO1/ADC_I1_MCD_71") (pintype "bidirectional+no_connect"))
    )
    (net (code "72") (name "unconnected-(U10-GPIO2{slash}ADC_VM_MCD-Pad74)") (class "Default")
      (node (ref "U10") (pin "74") (pinfunction "GPIO2/ADC_VM_MCD_74") (pintype "bidirectional+no_connect"))
    )
    (net (code "73") (name "unconnected-(U10-PWM_I-Pad58)") (class "Default")
      (node (ref "U10") (pin "58") (pinfunction "PWM_I_58") (pintype "input+no_connect"))
    )
    (net (code "74") (name "unconnected-(U10-PWM_Y2_H-Pad48)") (class "Default")
      (node (ref "U10") (pin "48") (pinfunction "PWM_Y2_H_48") (pintype "output+no_connect"))
    )
    (net (code "75") (name "unconnected-(U10-PWM_Y2_L-Pad49)") (class "Default")
      (node (ref "U10") (pin "49") (pinfunction "PWM_Y2_L_49") (pintype "output+no_connect"))
    )
    (net (code "76") (name "unconnected-(U10-REF_H-Pad68)") (class "Default")
      (node (ref "U10") (pin "68") (pinfunction "REF_H_68") (pintype "input+no_connect"))
    )
    (net (code "77") (name "unconnected-(U10-REF_L-Pad67)") (class "Default")
      (node (ref "U10") (pin "67") (pinfunction "REF_L_67") (pintype "input+no_connect"))
    )
    (net (code "78") (name "unconnected-(U10-REF_R-Pad69)") (class "Default")
      (node (ref "U10") (pin "69") (pinfunction "REF_R_69") (pintype "input+no_connect"))
    )
    (net (code "79") (name "unconnected-(U10-STATUS-Pad12)") (class "Default")
      (node (ref "U10") (pin "12") (pinfunction "STATUS_12") (pintype "output+no_connect"))
    )
    (net (code "80") (name "unconnected-(U10-STEP-Pad57)") (class "Default")
      (node (ref "U10") (pin "57") (pinfunction "STEP_57") (pintype "input+no_connect"))
    )
    (net (code "81") (name "unconnected-(U10-UART_RXD-Pad10)") (class "Default")
      (node (ref "U10") (pin "10") (pinfunction "UART_RXD_10") (pintype "input+no_connect"))
    )
    (net (code "82") (name "unconnected-(U10-UART_TXD-Pad11)") (class "Default")
      (node (ref "U10") (pin "11") (pinfunction "UART_TXD_11") (pintype "output+no_connect"))
    )
  )
)
